# Thermokoppel.net
KiCad netlist of a schematic drawn in Altium Designer
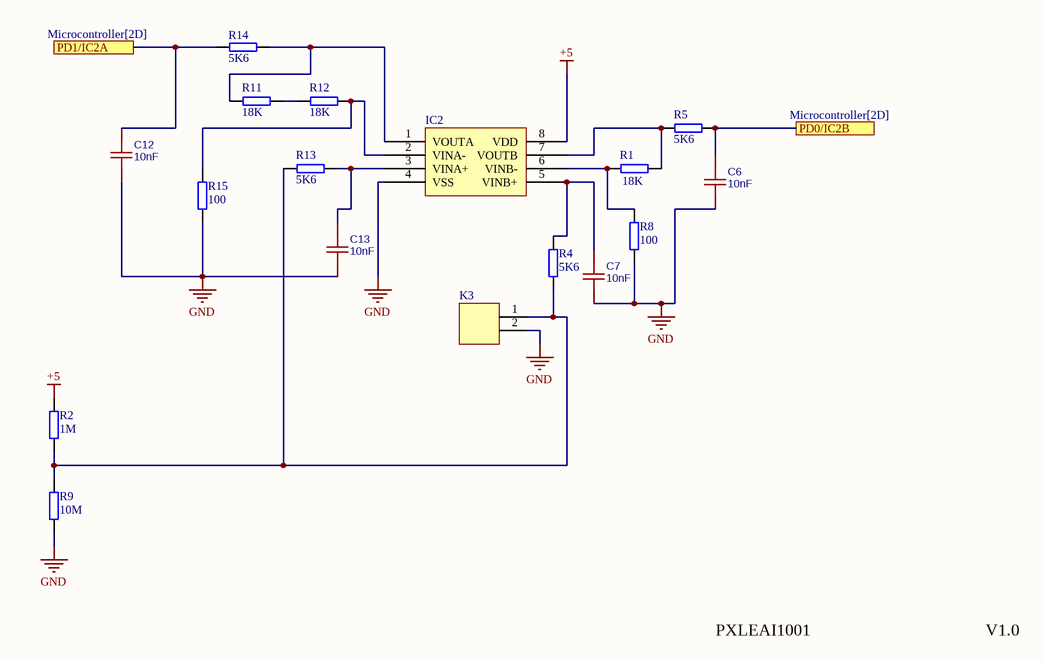
[diagram p0: Thermokoppel.SchDoc]

(export (version "E")
  (design (tool "Eeschema 10.0.6"))
  (components
    (comp (ref "C6")
      (value "10nF")
      (footprint "C6,7,12,13 10nF")
      (fields
        (field (name "BOM_SUPPLIER PART") "C376921")
        (field (name "BOM_MANUFACTURER PART") "TCC0805X7R103M500DT")
        (field (name "CONTRIBUTOR") "LCSC")
      )
      (libsource (lib "SoldeerStation") (part "C6,7,12,13 10nF"))
    )
    (comp (ref "C7")
      (value "10nF")
      (footprint "C6,7,12,13 10nF")
      (fields
        (field (name "BOM_SUPPLIER PART") "C376921")
        (field (name "BOM_MANUFACTURER PART") "TCC0805X7R103M500DT")
        (field (name "CONTRIBUTOR") "LCSC")
      )
      (libsource (lib "SoldeerStation") (part "C6,7,12,13 10nF"))
    )
    (comp (ref "C12")
      (value "10nF")
      (footprint "C6,7,12,13 10nF")
      (fields
        (field (name "BOM_SUPPLIER PART") "C376921")
        (field (name "BOM_MANUFACTURER PART") "TCC0805X7R103M500DT")
        (field (name "CONTRIBUTOR") "LCSC")
      )
      (libsource (lib "SoldeerStation") (part "C6,7,12,13 10nF"))
    )
    (comp (ref "C13")
      (value "10nF")
      (footprint "C6,7,12,13 10nF")
      (fields
        (field (name "BOM_SUPPLIER PART") "C376921")
        (field (name "BOM_MANUFACTURER PART") "TCC0805X7R103M500DT")
        (field (name "CONTRIBUTOR") "LCSC")
      )
      (libsource (lib "SoldeerStation") (part "C6,7,12,13 10nF"))
    )
    (comp (ref "IC2")
      (value "~")
      (footprint "IC2 opamps")
      (description "IC2 dual opamps")
      (libsource (lib "SoldeerStation") (part "IC2 dual opamps"))
    )
    (comp (ref "K3")
      (value "~")
      (footprint "Terminal_2")
      (libsource (lib "SoldeerStation") (part "K Terminal_2"))
    )
    (comp (ref "R1")
      (value "18K")
      (footprint "RESC2013X50X30ML20T20")
      (fields (field (name "MANUFACTURER") "Vishay Dale") (field (name "PART NUMBER") "CRCW08050000Z0EA"))
      (libsource (lib "") (part "R Resistor_1"))
    )
    (comp (ref "R2")
      (value "1M")
      (footprint "RESC2013X50X30ML20T20")
      (fields (field (name "MANUFACTURER") "Vishay Dale") (field (name "PART NUMBER") "CRCW08050000Z0EA"))
      (libsource (lib "") (part "R Resistor_1"))
    )
    (comp (ref "R4")
      (value "5K6")
      (footprint "RESC2013X50X30ML20T20")
      (fields (field (name "MANUFACTURER") "Vishay Dale") (field (name "PART NUMBER") "CRCW08050000Z0EA"))
      (libsource (lib "SoldeerStation") (part "R Resistor"))
    )
    (comp (ref "R5")
      (value "5K6")
      (footprint "RESC2013X50X30ML20T20")
      (fields (field (name "MANUFACTURER") "Vishay Dale") (field (name "PART NUMBER") "CRCW08050000Z0EA"))
      (libsource (lib "SoldeerStation") (part "R Resistor"))
    )
    (comp (ref "R8")
      (value "100")
      (footprint "RESC2013X50X30ML20T20")
      (fields (field (name "MANUFACTURER") "Vishay Dale") (field (name "PART NUMBER") "CRCW08050000Z0EA"))
      (libsource (lib "") (part "R Resistor_1"))
    )
    (comp (ref "R9")
      (value "10M")
      (footprint "RESC2013X50X30ML20T20")
      (fields (field (name "MANUFACTURER") "Vishay Dale") (field (name "PART NUMBER") "CRCW08050000Z0EA"))
      (libsource (lib "") (part "R Resistor_1"))
    )
    (comp (ref "R11")
      (value "18K")
      (footprint "RESC2013X50X30ML20T20")
      (fields (field (name "MANUFACTURER") "Vishay Dale") (field (name "PART NUMBER") "CRCW08050000Z0EA"))
      (libsource (lib "") (part "R Resistor_1"))
    )
    (comp (ref "R12")
      (value "18K")
      (footprint "RESC2013X50X30ML20T20")
      (fields (field (name "MANUFACTURER") "Vishay Dale") (field (name "PART NUMBER") "CRCW08050000Z0EA"))
      (libsource (lib "") (part "R Resistor_1"))
    )
    (comp (ref "R13")
      (value "5K6")
      (footprint "RESC2013X50X30ML20T20")
      (fields (field (name "MANUFACTURER") "Vishay Dale") (field (name "PART NUMBER") "CRCW08050000Z0EA"))
      (libsource (lib "SoldeerStation") (part "R Resistor"))
    )
    (comp (ref "R14")
      (value "5K6")
      (footprint "RESC2013X50X30ML20T20")
      (fields (field (name "MANUFACTURER") "Vishay Dale") (field (name "PART NUMBER") "CRCW08050000Z0EA"))
      (libsource (lib "") (part "R Resistor_1"))
    )
    (comp (ref "R15")
      (value "100")
      (footprint "RESC2013X50X30ML20T20")
      (fields (field (name "MANUFACTURER") "Vishay Dale") (field (name "PART NUMBER") "CRCW08050000Z0EA"))
      (libsource (lib "") (part "R Resistor_1"))
    )
  )
  (nets
    (net (code "1") (name "+5") (class "Default")
      (node (ref "IC2") (pin "8") (pinfunction "VDD_8") (pintype "passive"))
      (node (ref "R2") (pin "2") (pinfunction "2_2") (pintype "passive"))
    )
    (net (code "2") (name "/PD0{slash}IC2B") (class "Default")
      (node (ref "C6") (pin "2") (pinfunction "2_2") (pintype "passive"))
      (node (ref "R5") (pin "1") (pinfunction "1_1") (pintype "passive"))
    )
    (net (code "3") (name "/PD1{slash}IC2A") (class "Default")
      (node (ref "C12") (pin "2") (pinfunction "2_2") (pintype "passive"))
      (node (ref "R14") (pin "1") (pinfunction "1_1") (pintype "passive"))
    )
    (net (code "4") (name "GND") (class "Default")
      (node (ref "C12") (pin "1") (pinfunction "1_1") (pintype "passive"))
      (node (ref "C13") (pin "1") (pinfunction "1_1") (pintype "passive"))
      (node (ref "C6") (pin "1") (pinfunction "1_1") (pintype "passive"))
      (node (ref "C7") (pin "1") (pinfunction "1_1") (pintype "passive"))
      (node (ref "IC2") (pin "4") (pinfunction "VSS_4") (pintype "passive"))
      (node (ref "K3") (pin "2") (pintype "passive"))
      (node (ref "R15") (pin "1") (pinfunction "1_1") (pintype "passive"))
      (node (ref "R8") (pin "1") (pinfunction "1_1") (pintype "passive"))
      (node (ref "R9") (pin "1") (pinfunction "1_1") (pintype "passive"))
    )
    (net (code "5") (name "Net-(IC2-VINA+)") (class "Default")
      (node (ref "C13") (pin "2") (pinfunction "2_2") (pintype "passive"))
      (node (ref "IC2") (pin "3") (pinfunction "VINA+_3") (pintype "passive"))
      (node (ref "R13") (pin "2") (pinfunction "2_2") (pintype "passive"))
    )
    (net (code "6") (name "Net-(IC2-VINA-)") (class "Default")
      (node (ref "IC2") (pin "2") (pinfunction "VINA-_2") (pintype "passive"))
      (node (ref "R12") (pin "2") (pinfunction "2_2") (pintype "passive"))
      (node (ref "R15") (pin "2") (pinfunction "2_2") (pintype "passive"))
    )
    (net (code "7") (name "Net-(IC2-VINB+)") (class "Default")
      (node (ref "C7") (pin "2") (pinfunction "2_2") (pintype "passive"))
      (node (ref "IC2") (pin "5") (pinfunction "VINB+_5") (pintype "passive"))
      (node (ref "R4") (pin "1") (pinfunction "1_1") (pintype "passive"))
    )
    (net (code "8") (name "Net-(IC2-VINB-)") (class "Default")
      (node (ref "IC2") (pin "6") (pinfunction "VINB-_6") (pintype "passive"))
      (node (ref "R1") (pin "1") (pinfunction "1_1") (pintype "passive"))
      (node (ref "R8") (pin "2") (pinfunction "2_2") (pintype "passive"))
    )
    (net (code "9") (name "Net-(IC2-VOUTA)") (class "Default")
      (node (ref "IC2") (pin "1") (pinfunction "VOUTA_1") (pintype "passive"))
      (node (ref "R11") (pin "2") (pinfunction "2_2") (pintype "passive"))
      (node (ref "R14") (pin "2") (pinfunction "2_2") (pintype "passive"))
    )
    (net (code "10") (name "Net-(IC2-VOUTB)") (class "Default")
      (node (ref "IC2") (pin "7") (pinfunction "VOUTB_7") (pintype "passive"))
      (node (ref "R1") (pin "2") (pinfunction "2_2") (pintype "passive"))
      (node (ref "R5") (pin "2") (pinfunction "2_2") (pintype "passive"))
    )
    (net (code "11") (name "Net-(K3-Pad1)") (class "Default")
      (node (ref "K3") (pin "1") (pintype "passive"))
      (node (ref "R13") (pin "1") (pinfunction "1_1") (pintype "passive"))
      (node (ref "R2") (pin "1") (pinfunction "1_1") (pintype "passive"))
      (node (ref "R4") (pin "2") (pinfunction "2_2") (pintype "passive"))
      (node (ref "R9") (pin "2") (pinfunction "2_2") (pintype "passive"))
    )
    (net (code "12") (name "Net-(R11-Pad1)") (class "Default")
      (node (ref "R11") (pin "1") (pinfunction "1_1") (pintype "passive"))
      (node (ref "R12") (pin "1") (pinfunction "1_1") (pintype "passive"))
    )
  )
)
